# microcontroller.net
KiCad netlist of a schematic drawn in Altium Designer
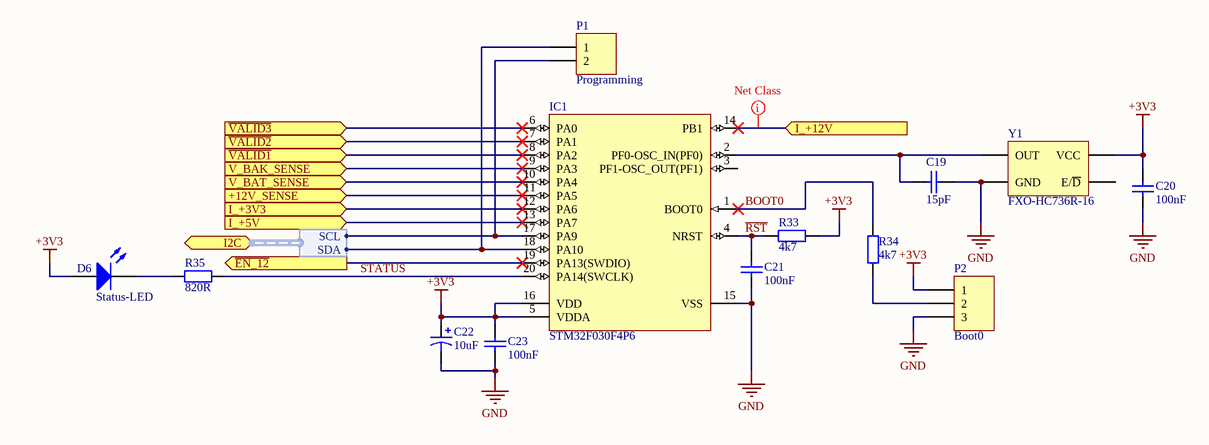
[diagram p0: microcontroller.SchDoc]

(export (version "E")
  (design (tool "Eeschema 10.0.6"))
  (components
    (comp (ref "C19")
      (value "15pF")
      (footprint "C2012")
      (description "Capacitor")
      (fields
        (field (name "MANUFACTURER") "MULTICOMP")
        (field (name "MANUFACTURER PART NUMBER") "MC0805N150J500CT")
        (field (name "PUBLISHER") "Altium Limited")
      )
      (libsource (lib "Miscellaneous Devices") (part "Cap"))
    )
    (comp (ref "C20")
      (value "100nF")
      (footprint "C2012")
      (description "Capacitor")
      (fields (field (name "PUBLISHER") "Altium Limited"))
      (libsource (lib "Miscellaneous Devices") (part "Cap"))
    )
    (comp (ref "C21")
      (value "100nF")
      (footprint "C2012")
      (description "Capacitor")
      (fields (field (name "PUBLISHER") "Altium Limited"))
      (libsource (lib "Miscellaneous Devices") (part "Cap"))
    )
    (comp (ref "C22")
      (value "10uF")
      (footprint "C2012")
      (description "Polarized Capacitor (Radial)")
      (fields (field (name "PUBLISHER") "Altium Limited"))
      (libsource (lib "Miscellaneous Devices") (part "Cap Pol1"))
    )
    (comp (ref "C23")
      (value "100nF")
      (footprint "C2012")
      (description "Capacitor")
      (fields (field (name "PUBLISHER") "Altium Limited"))
      (libsource (lib "Miscellaneous Devices") (part "Cap"))
    )
    (comp (ref "D6")
      (value "Status-LED")
      (footprint "MLCC2")
      (description "Green")
      (fields (field (name "PUBLISHER") "Altium Limited"))
      (libsource (lib "Miscellaneous Devices") (part "LED0"))
    )
    (comp (ref "IC1")
      (value "STM32F030F4P6")
      (footprint "STM-TSSOP20_L")
      (libsource (lib "Altium Content Vault") (part "CMP-0304-00039-2"))
    )
    (comp (ref "P1")
      (value "Programming")
      (footprint "HDR1X2")
      (description "Header, 2-Pin")
      (fields (field (name "PUBLISHER") "Altium Limited"))
      (libsource (lib "Miscellaneous Connectors") (part "Header 2"))
    )
    (comp (ref "P2")
      (value "Boot0")
      (footprint "HDR1X3")
      (description "Header, 3-Pin")
      (fields (field (name "PUBLISHER") "Altium Limited"))
      (libsource (lib "Miscellaneous Connectors") (part "Header 3"))
    )
    (comp (ref "R33")
      (value "4k7")
      (footprint "R2012")
      (description "Resistor")
      (fields (field (name "PUBLISHER") "Altium Limited"))
      (libsource (lib "Miscellaneous Devices") (part "Res2"))
    )
    (comp (ref "R34")
      (value "4k7")
      (footprint "R2012")
      (description "Resistor")
      (fields (field (name "PUBLISHER") "Altium Limited"))
      (libsource (lib "") (part "Res2_2"))
    )
    (comp (ref "R35")
      (value "820R")
      (footprint "R2012")
      (description "Resistor")
      (fields (field (name "PUBLISHER") "Altium Limited"))
      (libsource (lib "") (part "Res2_1"))
    )
    (comp (ref "Y1")
      (value "FXO-HC736R-16")
      (footprint "FXO-HC73")
      (description "Oscillator with Enable Input")
      (libsource (lib "bitbots") (part "Oszillator"))
    )
  )
  (nets
    (net (code "2") (name "+3V3") (class "Default")
      (node (ref "C20") (pin "1") (pinfunction "1_1") (pintype "passive"))
      (node (ref "C22") (pin "1") (pinfunction "1_1") (pintype "passive"))
      (node (ref "C23") (pin "2") (pinfunction "2_2") (pintype "passive"))
      (node (ref "D6") (pin "1") (pinfunction "A_1") (pintype "passive"))
      (node (ref "IC1") (pin "16") (pinfunction "VDD_16") (pintype "power_in"))
      (node (ref "IC1") (pin "5") (pinfunction "VDDA_5") (pintype "power_in"))
      (node (ref "P2") (pin "1") (pinfunction "1_1") (pintype "passive"))
      (node (ref "R33") (pin "1") (pinfunction "1_1") (pintype "passive"))
      (node (ref "Y1") (pin "4") (pinfunction "VCC_4") (pintype "passive"))
    )
    (net (code "3") (name "/+12V_SENSE") (class "Default")
      (node (ref "IC1") (pin "11") (pinfunction "PA5_11") (pintype "bidirectional+no_connect"))
    )
    (net (code "4") (name "/BOOT0") (class "Default")
      (node (ref "IC1") (pin "1") (pinfunction "BOOT0_1") (pintype "input"))
      (node (ref "R34") (pin "1") (pinfunction "1_1") (pintype "passive"))
    )
    (net (code "5") (name "/EN_12") (class "Default")
      (node (ref "IC1") (pin "19") (pinfunction "PA13(SWDIO)_19") (pintype "bidirectional+no_connect"))
    )
    (net (code "6") (name "/I_+3V3") (class "Default")
      (node (ref "IC1") (pin "12") (pinfunction "PA6_12") (pintype "bidirectional+no_connect"))
    )
    (net (code "7") (name "/I_+5V") (class "Default")
      (node (ref "IC1") (pin "13") (pinfunction "PA7_13") (pintype "bidirectional+no_connect"))
    )
    (net (code "8") (name "/I_+12V") (class "Default")
      (node (ref "IC1") (pin "14") (pinfunction "PB1_14") (pintype "bidirectional+no_connect"))
    )
    (net (code "9") (name "/RST") (class "Default")
      (node (ref "C21") (pin "2") (pinfunction "2_2") (pintype "passive"))
      (node (ref "IC1") (pin "4") (pinfunction "NRST_4") (pintype "bidirectional"))
      (node (ref "R33") (pin "2") (pinfunction "2_2") (pintype "passive"))
    )
    (net (code "10") (name "/STATUS") (class "Default")
      (node (ref "IC1") (pin "20") (pinfunction "PA14(SWCLK)_20") (pintype "bidirectional"))
      (node (ref "R35") (pin "2") (pinfunction "2_2") (pintype "passive"))
    )
    (net (code "11") (name "/VALID1") (class "Default")
      (node (ref "IC1") (pin "8") (pinfunction "PA2_8") (pintype "bidirectional+no_connect"))
    )
    (net (code "12") (name "/VALID2") (class "Default")
      (node (ref "IC1") (pin "7") (pinfunction "PA1_7") (pintype "bidirectional+no_connect"))
    )
    (net (code "13") (name "/VALID3") (class "Default")
      (node (ref "IC1") (pin "6") (pinfunction "PA0_6") (pintype "bidirectional+no_connect"))
    )
    (net (code "14") (name "/V_BAK_SENSE") (class "Default")
      (node (ref "IC1") (pin "9") (pinfunction "PA3_9") (pintype "bidirectional+no_connect"))
    )
    (net (code "15") (name "/V_BAT_SENSE") (class "Default")
      (node (ref "IC1") (pin "10") (pinfunction "PA4_10") (pintype "bidirectional+no_connect"))
    )
    (net (code "17") (name "GND") (class "Default")
      (node (ref "C19") (pin "1") (pinfunction "1_1") (pintype "passive"))
      (node (ref "C20") (pin "2") (pinfunction "2_2") (pintype "passive"))
      (node (ref "C21") (pin "1") (pinfunction "1_1") (pintype "passive"))
      (node (ref "C22") (pin "2") (pinfunction "2_2") (pintype "passive"))
      (node (ref "C23") (pin "1") (pinfunction "1_1") (pintype "passive"))
      (node (ref "IC1") (pin "15") (pinfunction "VSS_15") (pintype "power_in"))
      (node (ref "P2") (pin "3") (pinfunction "3_3") (pintype "passive"))
      (node (ref "Y1") (pin "2") (pinfunction "GND_2") (pintype "passive"))
    )
    (net (code "18") (name "Net-(D6-K)") (class "Default")
      (node (ref "D6") (pin "2") (pinfunction "K_2") (pintype "passive"))
      (node (ref "R35") (pin "1") (pinfunction "1_1") (pintype "passive"))
    )
    (net (code "19") (name "Net-(IC1-PA9)") (class "Default")
      (node (ref "IC1") (pin "17") (pinfunction "PA9_17") (pintype "bidirectional"))
      (node (ref "P1") (pin "2") (pinfunction "2_2") (pintype "passive"))
    )
    (net (code "20") (name "Net-(IC1-PA10)") (class "Default")
      (node (ref "IC1") (pin "18") (pinfunction "PA10_18") (pintype "bidirectional"))
      (node (ref "P1") (pin "1") (pinfunction "1_1") (pintype "passive"))
    )
    (net (code "21") (name "Net-(IC1-PF0-OSC_IN(PF0))") (class "Default")
      (node (ref "C19") (pin "2") (pinfunction "2_2") (pintype "passive"))
      (node (ref "IC1") (pin "2") (pinfunction "PF0-OSC_IN(PF0)_2") (pintype "bidirectional"))
      (node (ref "Y1") (pin "3") (pinfunction "OUT_3") (pintype "passive"))
    )
    (net (code "22") (name "Net-(P2-Pad2)") (class "Default")
      (node (ref "P2") (pin "2") (pinfunction "2_2") (pintype "passive"))
      (node (ref "R34") (pin "2") (pinfunction "2_2") (pintype "passive"))
    )
    (net (code "23") (name "unconnected-(IC1-PF1-OSC_OUT(PF1)-Pad3)") (class "Default")
      (node (ref "IC1") (pin "3") (pinfunction "PF1-OSC_OUT(PF1)_3") (pintype "bidirectional"))
    )
    (net (code "24") (name "unconnected-(Y1-E{slash}~{D}-Pad1)") (class "Default")
      (node (ref "Y1") (pin "1") (pinfunction "E/~{D}_1") (pintype "passive"))
    )
  )
)
